# Sheet5.net
KiCad netlist of a schematic drawn in Altium Designer
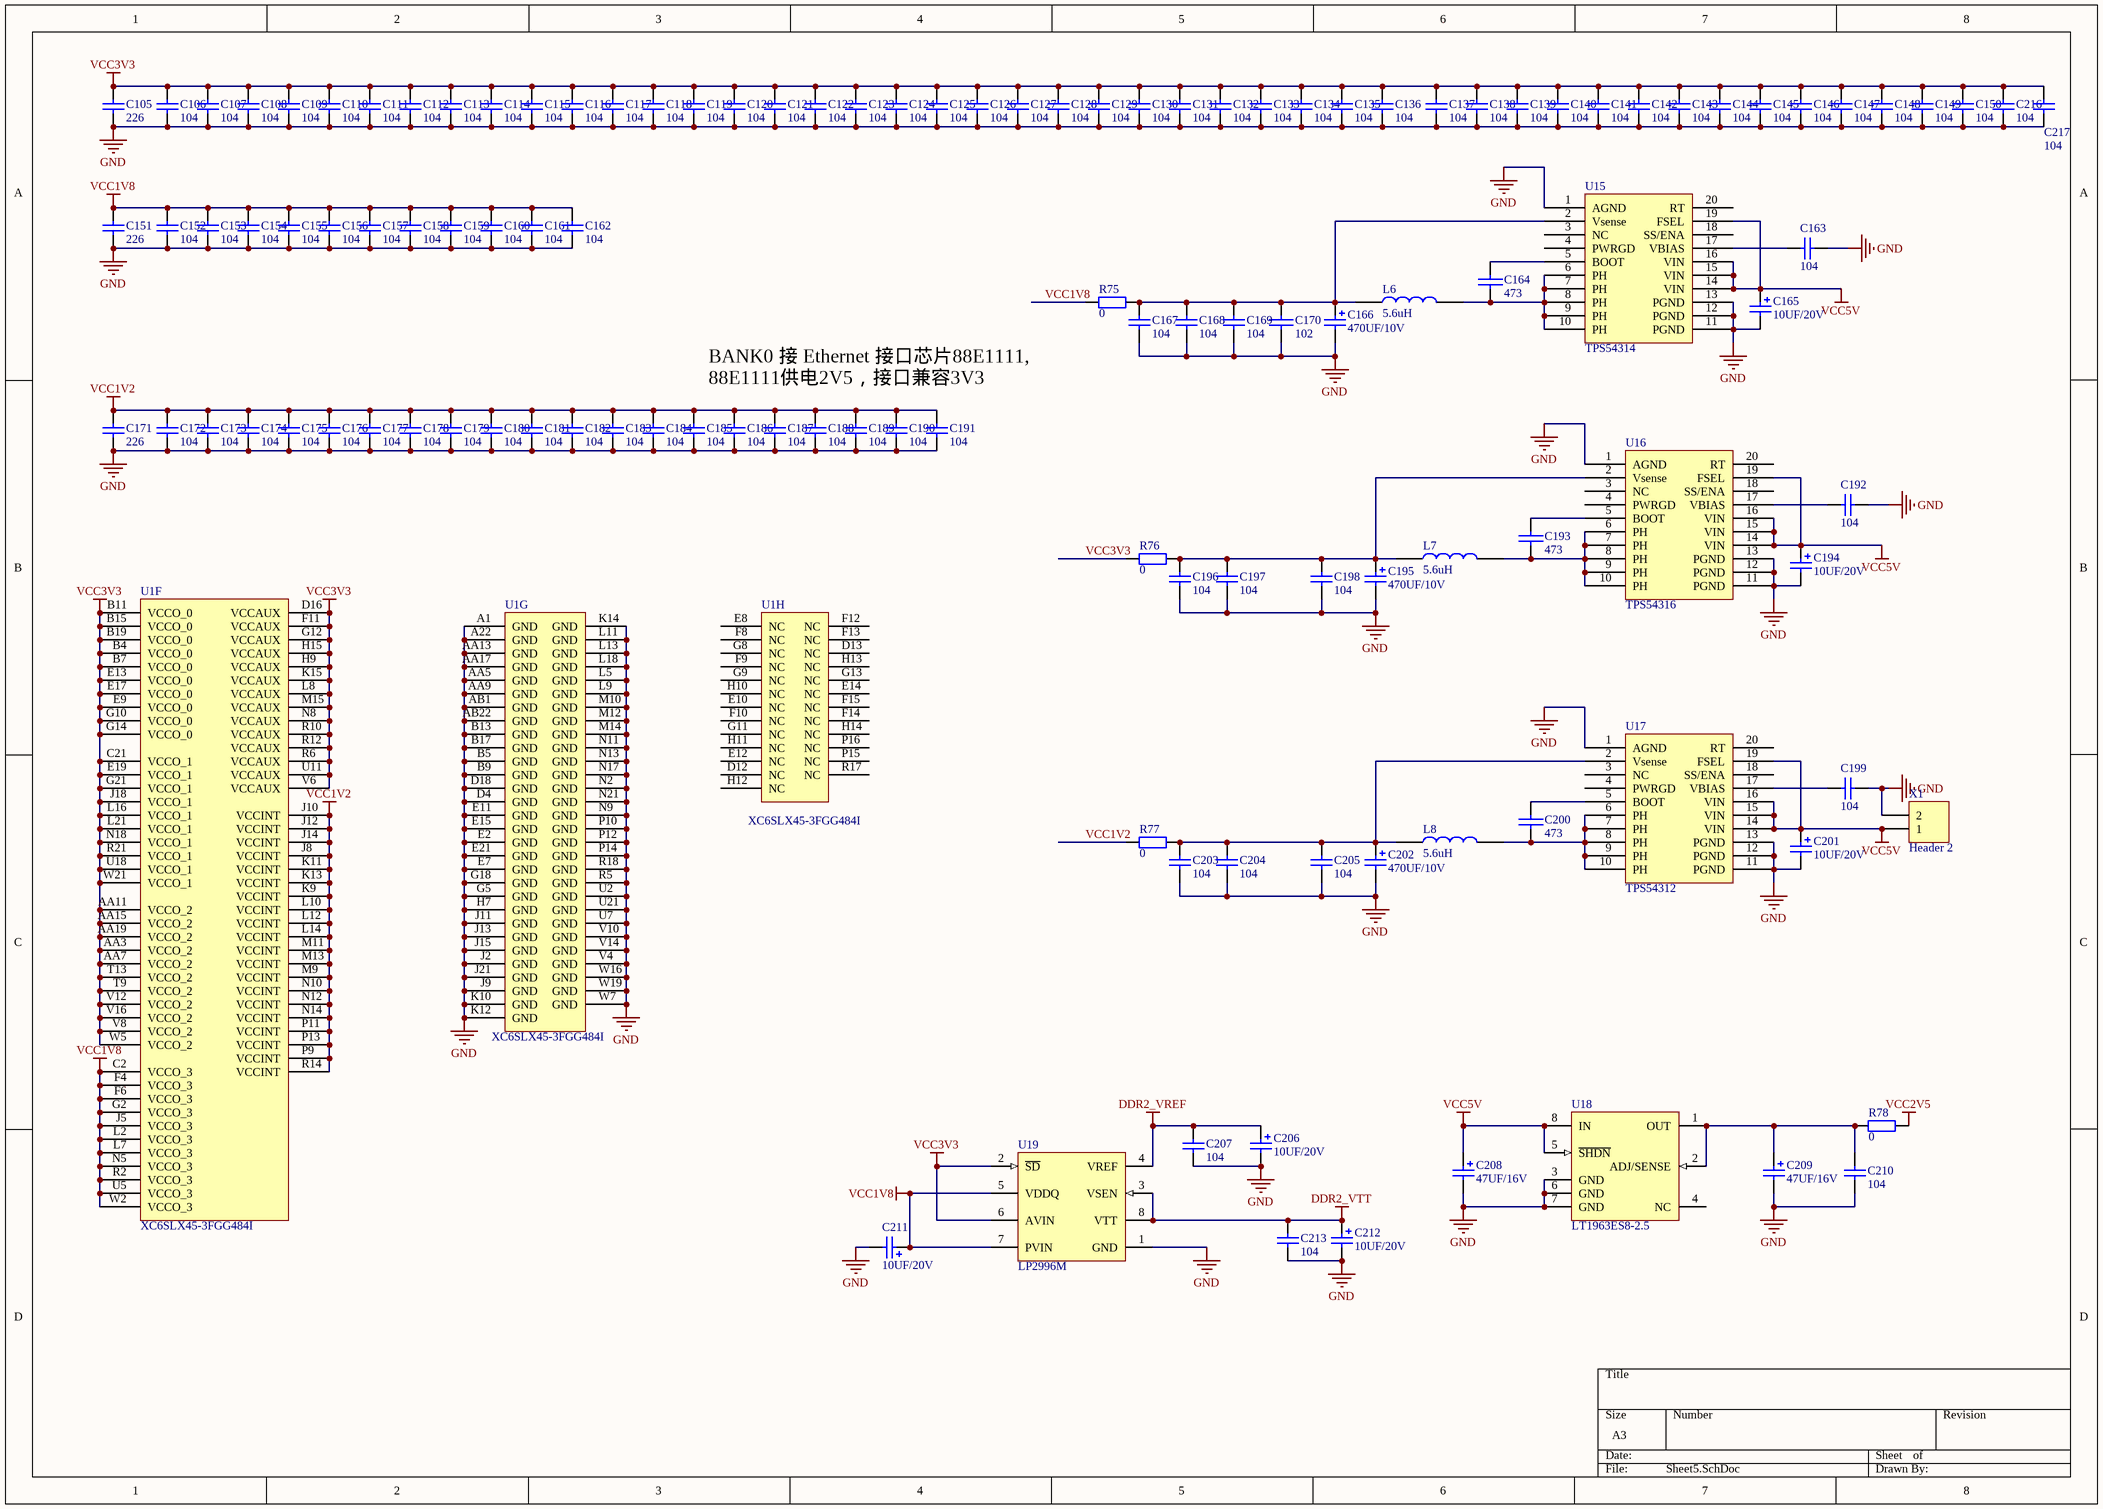
[diagram p0: Sheet5.SchDoc]

(export (version "E")
  (design (tool "Eeschema 10.0.6"))
  (components
    (comp (ref "C105")
      (value "226")
      (footprint "0603")
      (description "Capacitor")
      (fields (field (name "PUBLISHER") "Altium Limited"))
      (libsource (lib "Miscellaneous Devices") (part "Cap"))
    )
    (comp (ref "C106")
      (value "104")
      (footprint "0402")
      (description "Capacitor")
      (fields (field (name "PUBLISHER") "Altium Limited"))
      (libsource (lib "Miscellaneous Devices") (part "Cap"))
    )
    (comp (ref "C107")
      (value "104")
      (footprint "0402")
      (description "Capacitor")
      (fields (field (name "PUBLISHER") "Altium Limited"))
      (libsource (lib "Miscellaneous Devices") (part "Cap"))
    )
    (comp (ref "C108")
      (value "104")
      (footprint "0402")
      (description "Capacitor")
      (fields (field (name "PUBLISHER") "Altium Limited"))
      (libsource (lib "Miscellaneous Devices") (part "Cap"))
    )
    (comp (ref "C109")
      (value "104")
      (footprint "0402")
      (description "Capacitor")
      (fields (field (name "PUBLISHER") "Altium Limited"))
      (libsource (lib "Miscellaneous Devices") (part "Cap"))
    )
    (comp (ref "C110")
      (value "104")
      (footprint "0402")
      (description "Capacitor")
      (fields (field (name "PUBLISHER") "Altium Limited"))
      (libsource (lib "Miscellaneous Devices") (part "Cap"))
    )
    (comp (ref "C111")
      (value "104")
      (footprint "0402")
      (description "Capacitor")
      (fields (field (name "PUBLISHER") "Altium Limited"))
      (libsource (lib "Miscellaneous Devices") (part "Cap"))
    )
    (comp (ref "C112")
      (value "104")
      (footprint "0402")
      (description "Capacitor")
      (fields (field (name "PUBLISHER") "Altium Limited"))
      (libsource (lib "Miscellaneous Devices") (part "Cap"))
    )
    (comp (ref "C113")
      (value "104")
      (footprint "0402")
      (description "Capacitor")
      (fields (field (name "PUBLISHER") "Altium Limited"))
      (libsource (lib "Miscellaneous Devices") (part "Cap"))
    )
    (comp (ref "C114")
      (value "104")
      (footprint "0402")
      (description "Capacitor")
      (fields (field (name "PUBLISHER") "Altium Limited"))
      (libsource (lib "Miscellaneous Devices") (part "Cap"))
    )
    (comp (ref "C115")
      (value "104")
      (footprint "0402")
      (description "Capacitor")
      (fields (field (name "PUBLISHER") "Altium Limited"))
      (libsource (lib "Miscellaneous Devices") (part "Cap"))
    )
    (comp (ref "C116")
      (value "104")
      (footprint "0402")
      (description "Capacitor")
      (fields (field (name "PUBLISHER") "Altium Limited"))
      (libsource (lib "Miscellaneous Devices") (part "Cap"))
    )
    (comp (ref "C117")
      (value "104")
      (footprint "0402")
      (description "Capacitor")
      (fields (field (name "PUBLISHER") "Altium Limited"))
      (libsource (lib "Miscellaneous Devices") (part "Cap"))
    )
    (comp (ref "C118")
      (value "104")
      (footprint "0402")
      (description "Capacitor")
      (fields (field (name "PUBLISHER") "Altium Limited"))
      (libsource (lib "Miscellaneous Devices") (part "Cap"))
    )
    (comp (ref "C119")
      (value "104")
      (footprint "0402")
      (description "Capacitor")
      (fields (field (name "PUBLISHER") "Altium Limited"))
      (libsource (lib "Miscellaneous Devices") (part "Cap"))
    )
    (comp (ref "C120")
      (value "104")
      (footprint "0402")
      (description "Capacitor")
      (fields (field (name "PUBLISHER") "Altium Limited"))
      (libsource (lib "Miscellaneous Devices") (part "Cap"))
    )
    (comp (ref "C121")
      (value "104")
      (footprint "0402")
      (description "Capacitor")
      (fields (field (name "PUBLISHER") "Altium Limited"))
      (libsource (lib "Miscellaneous Devices") (part "Cap"))
    )
    (comp (ref "C122")
      (value "104")
      (footprint "0402")
      (description "Capacitor")
      (fields (field (name "PUBLISHER") "Altium Limited"))
      (libsource (lib "Miscellaneous Devices") (part "Cap"))
    )
    (comp (ref "C123")
      (value "104")
      (footprint "0402")
      (description "Capacitor")
      (fields (field (name "PUBLISHER") "Altium Limited"))
      (libsource (lib "Miscellaneous Devices") (part "Cap"))
    )
    (comp (ref "C124")
      (value "104")
      (footprint "0402")
      (description "Capacitor")
      (fields (field (name "PUBLISHER") "Altium Limited"))
      (libsource (lib "Miscellaneous Devices") (part "Cap"))
    )
    (comp (ref "C125")
      (value "104")
      (footprint "0402")
      (description "Capacitor")
      (fields (field (name "PUBLISHER") "Altium Limited"))
      (libsource (lib "Miscellaneous Devices") (part "Cap"))
    )
    (comp (ref "C126")
      (value "104")
      (footprint "0402")
      (description "Capacitor")
      (fields (field (name "PUBLISHER") "Altium Limited"))
      (libsource (lib "Miscellaneous Devices") (part "Cap"))
    )
    (comp (ref "C127")
      (value "104")
      (footprint "0402")
      (description "Capacitor")
      (fields (field (name "PUBLISHER") "Altium Limited"))
      (libsource (lib "Miscellaneous Devices") (part "Cap"))
    )
    (comp (ref "C128")
      (value "104")
      (footprint "0402")
      (description "Capacitor")
      (fields (field (name "PUBLISHER") "Altium Limited"))
      (libsource (lib "Miscellaneous Devices") (part "Cap"))
    )
    (comp (ref "C129")
      (value "104")
      (footprint "0402")
      (description "Capacitor")
      (fields (field (name "PUBLISHER") "Altium Limited"))
      (libsource (lib "Miscellaneous Devices") (part "Cap"))
    )
    (comp (ref "C130")
      (value "104")
      (footprint "0402")
      (description "Capacitor")
      (fields (field (name "PUBLISHER") "Altium Limited"))
      (libsource (lib "Miscellaneous Devices") (part "Cap"))
    )
    (comp (ref "C131")
      (value "104")
      (footprint "0402")
      (description "Capacitor")
      (fields (field (name "PUBLISHER") "Altium Limited"))
      (libsource (lib "Miscellaneous Devices") (part "Cap"))
    )
    (comp (ref "C132")
      (value "104")
      (footprint "0402")
      (description "Capacitor")
      (fields (field (name "PUBLISHER") "Altium Limited"))
      (libsource (lib "Miscellaneous Devices") (part "Cap"))
    )
    (comp (ref "C133")
      (value "104")
      (footprint "0402")
      (description "Capacitor")
      (fields (field (name "PUBLISHER") "Altium Limited"))
      (libsource (lib "Miscellaneous Devices") (part "Cap"))
    )
    (comp (ref "C134")
      (value "104")
      (footprint "0402")
      (description "Capacitor")
      (fields (field (name "PUBLISHER") "Altium Limited"))
      (libsource (lib "Miscellaneous Devices") (part "Cap"))
    )
    (comp (ref "C135")
      (value "104")
      (footprint "0402")
      (description "Capacitor")
      (fields (field (name "PUBLISHER") "Altium Limited"))
      (libsource (lib "Miscellaneous Devices") (part "Cap"))
    )
    (comp (ref "C136")
      (value "104")
      (footprint "0402")
      (description "Capacitor")
      (fields (field (name "PUBLISHER") "Altium Limited"))
      (libsource (lib "Miscellaneous Devices") (part "Cap"))
    )
    (comp (ref "C137")
      (value "104")
      (footprint "0402")
      (description "Capacitor")
      (fields (field (name "PUBLISHER") "Altium Limited"))
      (libsource (lib "Miscellaneous Devices") (part "Cap"))
    )
    (comp (ref "C138")
      (value "104")
      (footprint "0402")
      (description "Capacitor")
      (fields (field (name "PUBLISHER") "Altium Limited"))
      (libsource (lib "Miscellaneous Devices") (part "Cap"))
    )
    (comp (ref "C139")
      (value "104")
      (footprint "0402")
      (description "Capacitor")
      (fields (field (name "PUBLISHER") "Altium Limited"))
      (libsource (lib "Miscellaneous Devices") (part "Cap"))
    )
    (comp (ref "C140")
      (value "104")
      (footprint "0402")
      (description "Capacitor")
      (fields (field (name "PUBLISHER") "Altium Limited"))
      (libsource (lib "Miscellaneous Devices") (part "Cap"))
    )
    (comp (ref "C141")
      (value "104")
      (footprint "0402")
      (description "Capacitor")
      (fields (field (name "PUBLISHER") "Altium Limited"))
      (libsource (lib "Miscellaneous Devices") (part "Cap"))
    )
    (comp (ref "C142")
      (value "104")
      (footprint "0402")
      (description "Capacitor")
      (fields (field (name "PUBLISHER") "Altium Limited"))
      (libsource (lib "Miscellaneous Devices") (part "Cap"))
    )
    (comp (ref "C143")
      (value "104")
      (footprint "0402")
      (description "Capacitor")
      (fields (field (name "PUBLISHER") "Altium Limited"))
      (libsource (lib "Miscellaneous Devices") (part "Cap"))
    )
    (comp (ref "C144")
      (value "104")
      (footprint "0402")
      (description "Capacitor")
      (fields (field (name "PUBLISHER") "Altium Limited"))
      (libsource (lib "Miscellaneous Devices") (part "Cap"))
    )
    (comp (ref "C145")
      (value "104")
      (footprint "0402")
      (description "Capacitor")
      (fields (field (name "PUBLISHER") "Altium Limited"))
      (libsource (lib "Miscellaneous Devices") (part "Cap"))
    )
    (comp (ref "C146")
      (value "104")
      (footprint "0402")
      (description "Capacitor")
      (fields (field (name "PUBLISHER") "Altium Limited"))
      (libsource (lib "Miscellaneous Devices") (part "Cap"))
    )
    (comp (ref "C147")
      (value "104")
      (footprint "0402")
      (description "Capacitor")
      (fields (field (name "PUBLISHER") "Altium Limited"))
      (libsource (lib "Miscellaneous Devices") (part "Cap"))
    )
    (comp (ref "C148")
      (value "104")
      (footprint "0402")
      (description "Capacitor")
      (fields (field (name "PUBLISHER") "Altium Limited"))
      (libsource (lib "Miscellaneous Devices") (part "Cap"))
    )
    (comp (ref "C149")
      (value "104")
      (footprint "0402")
      (description "Capacitor")
      (fields (field (name "PUBLISHER") "Altium Limited"))
      (libsource (lib "Miscellaneous Devices") (part "Cap"))
    )
    (comp (ref "C150")
      (value "104")
      (footprint "0402")
      (description "Capacitor")
      (fields (field (name "PUBLISHER") "Altium Limited"))
      (libsource (lib "Miscellaneous Devices") (part "Cap"))
    )
    (comp (ref "C151")
      (value "226")
      (footprint "0603")
      (description "Capacitor")
      (fields (field (name "PUBLISHER") "Altium Limited"))
      (libsource (lib "Miscellaneous Devices") (part "Cap"))
    )
    (comp (ref "C152")
      (value "104")
      (footprint "0402")
      (description "Capacitor")
      (fields (field (name "PUBLISHER") "Altium Limited"))
      (libsource (lib "Miscellaneous Devices") (part "Cap"))
    )
    (comp (ref "C153")
      (value "104")
      (footprint "0402")
      (description "Capacitor")
      (fields (field (name "PUBLISHER") "Altium Limited"))
      (libsource (lib "Miscellaneous Devices") (part "Cap"))
    )
    (comp (ref "C154")
      (value "104")
      (footprint "0402")
      (description "Capacitor")
      (fields (field (name "PUBLISHER") "Altium Limited"))
      (libsource (lib "Miscellaneous Devices") (part "Cap"))
    )
    (comp (ref "C155")
      (value "104")
      (footprint "0402")
      (description "Capacitor")
      (fields (field (name "PUBLISHER") "Altium Limited"))
      (libsource (lib "Miscellaneous Devices") (part "Cap"))
    )
    (comp (ref "C156")
      (value "104")
      (footprint "0402")
      (description "Capacitor")
      (fields (field (name "PUBLISHER") "Altium Limited"))
      (libsource (lib "Miscellaneous Devices") (part "Cap"))
    )
    (comp (ref "C157")
      (value "104")
      (footprint "0402")
      (description "Capacitor")
      (fields (field (name "PUBLISHER") "Altium Limited"))
      (libsource (lib "Miscellaneous Devices") (part "Cap"))
    )
    (comp (ref "C158")
      (value "104")
      (footprint "0402")
      (description "Capacitor")
      (fields (field (name "PUBLISHER") "Altium Limited"))
      (libsource (lib "Miscellaneous Devices") (part "Cap"))
    )
    (comp (ref "C159")
      (value "104")
      (footprint "0402")
      (description "Capacitor")
      (fields (field (name "PUBLISHER") "Altium Limited"))
      (libsource (lib "Miscellaneous Devices") (part "Cap"))
    )
    (comp (ref "C160")
      (value "104")
      (footprint "0402")
      (description "Capacitor")
      (fields (field (name "PUBLISHER") "Altium Limited"))
      (libsource (lib "Miscellaneous Devices") (part "Cap"))
    )
    (comp (ref "C161")
      (value "104")
      (footprint "0402")
      (description "Capacitor")
      (fields (field (name "PUBLISHER") "Altium Limited"))
      (libsource (lib "Miscellaneous Devices") (part "Cap"))
    )
    (comp (ref "C162")
      (value "104")
      (footprint "0402")
      (description "Capacitor")
      (fields (field (name "PUBLISHER") "Altium Limited"))
      (libsource (lib "Miscellaneous Devices") (part "Cap"))
    )
    (comp (ref "C163")
      (value "104")
      (footprint "0402")
      (description "Capacitor")
      (fields (field (name "PUBLISHER") "Altium Limited"))
      (libsource (lib "Miscellaneous Devices") (part "Cap"))
    )
    (comp (ref "C164")
      (value "473")
      (footprint "0402")
      (description "Capacitor")
      (libsource (lib "*") (part "CAP"))
    )
    (comp (ref "C165")
      (value "10UF/20V")
      (footprint "CAP-B")
      (description "Polarized Capacitor (Axial)")
      (fields (field (name "PUBLISHER") "Altium Limited"))
      (libsource (lib "Miscellaneous Devices") (part "Cap Pol2"))
    )
    (comp (ref "C166")
      (value "470UF/10V")
      (footprint "CAP-D")
      (description "Polarized Capacitor (Axial)")
      (fields (field (name "PUBLISHER") "Altium Limited"))
      (libsource (lib "Miscellaneous Devices") (part "Cap Pol2"))
    )
    (comp (ref "C167")
      (value "104")
      (footprint "0402")
      (description "Capacitor")
      (fields (field (name "PUBLISHER") "Altium Limited"))
      (libsource (lib "Miscellaneous Devices") (part "Cap"))
    )
    (comp (ref "C168")
      (value "104")
      (footprint "0402")
      (description "Capacitor")
      (fields (field (name "PUBLISHER") "Altium Limited"))
      (libsource (lib "Miscellaneous Devices") (part "Cap"))
    )
    (comp (ref "C169")
      (value "104")
      (footprint "0402")
      (description "Capacitor")
      (fields (field (name "PUBLISHER") "Altium Limited"))
      (libsource (lib "Miscellaneous Devices") (part "Cap"))
    )
    (comp (ref "C170")
      (value "102")
      (footprint "0402")
      (description "Capacitor")
      (libsource (lib "*") (part "CAP"))
    )
    (comp (ref "C171")
      (value "226")
      (footprint "0603")
      (description "Capacitor")
      (fields (field (name "PUBLISHER") "Altium Limited"))
      (libsource (lib "Miscellaneous Devices") (part "Cap"))
    )
    (comp (ref "C172")
      (value "104")
      (footprint "0402")
      (description "Capacitor")
      (fields (field (name "PUBLISHER") "Altium Limited"))
      (libsource (lib "Miscellaneous Devices") (part "Cap"))
    )
    (comp (ref "C173")
      (value "104")
      (footprint "0402")
      (description "Capacitor")
      (fields (field (name "PUBLISHER") "Altium Limited"))
      (libsource (lib "Miscellaneous Devices") (part "Cap"))
    )
    (comp (ref "C174")
      (value "104")
      (footprint "0402")
      (description "Capacitor")
      (fields (field (name "PUBLISHER") "Altium Limited"))
      (libsource (lib "Miscellaneous Devices") (part "Cap"))
    )
    (comp (ref "C175")
      (value "104")
      (footprint "0402")
      (description "Capacitor")
      (fields (field (name "PUBLISHER") "Altium Limited"))
      (libsource (lib "Miscellaneous Devices") (part "Cap"))
    )
    (comp (ref "C176")
      (value "104")
      (footprint "0402")
      (description "Capacitor")
      (fields (field (name "PUBLISHER") "Altium Limited"))
      (libsource (lib "Miscellaneous Devices") (part "Cap"))
    )
    (comp (ref "C177")
      (value "104")
      (footprint "0402")
      (description "Capacitor")
      (fields (field (name "PUBLISHER") "Altium Limited"))
      (libsource (lib "Miscellaneous Devices") (part "Cap"))
    )
    (comp (ref "C178")
      (value "104")
      (footprint "0402")
      (description "Capacitor")
      (fields (field (name "PUBLISHER") "Altium Limited"))
      (libsource (lib "Miscellaneous Devices") (part "Cap"))
    )
    (comp (ref "C179")
      (value "104")
      (footprint "0402")
      (description "Capacitor")
      (fields (field (name "PUBLISHER") "Altium Limited"))
      (libsource (lib "Miscellaneous Devices") (part "Cap"))
    )
    (comp (ref "C180")
      (value "104")
      (footprint "0402")
      (description "Capacitor")
      (fields (field (name "PUBLISHER") "Altium Limited"))
      (libsource (lib "Miscellaneous Devices") (part "Cap"))
    )
    (comp (ref "C181")
      (value "104")
      (footprint "0402")
      (description "Capacitor")
      (fields (field (name "PUBLISHER") "Altium Limited"))
      (libsource (lib "Miscellaneous Devices") (part "Cap"))
    )
    (comp (ref "C182")
      (value "104")
      (footprint "0402")
      (description "Capacitor")
      (fields (field (name "PUBLISHER") "Altium Limited"))
      (libsource (lib "Miscellaneous Devices") (part "Cap"))
    )
    (comp (ref "C183")
      (value "104")
      (footprint "0402")
      (description "Capacitor")
      (fields (field (name "PUBLISHER") "Altium Limited"))
      (libsource (lib "Miscellaneous Devices") (part "Cap"))
    )
    (comp (ref "C184")
      (value "104")
      (footprint "0402")
      (description "Capacitor")
      (fields (field (name "PUBLISHER") "Altium Limited"))
      (libsource (lib "Miscellaneous Devices") (part "Cap"))
    )
    (comp (ref "C185")
      (value "104")
      (footprint "0402")
      (description "Capacitor")
      (fields (field (name "PUBLISHER") "Altium Limited"))
      (libsource (lib "Miscellaneous Devices") (part "Cap"))
    )
    (comp (ref "C186")
      (value "104")
      (footprint "0402")
      (description "Capacitor")
      (fields (field (name "PUBLISHER") "Altium Limited"))
      (libsource (lib "Miscellaneous Devices") (part "Cap"))
    )
    (comp (ref "C187")
      (value "104")
      (footprint "0402")
      (description "Capacitor")
      (fields (field (name "PUBLISHER") "Altium Limited"))
      (libsource (lib "Miscellaneous Devices") (part "Cap"))
    )
    (comp (ref "C188")
      (value "104")
      (footprint "0402")
      (description "Capacitor")
      (fields (field (name "PUBLISHER") "Altium Limited"))
      (libsource (lib "Miscellaneous Devices") (part "Cap"))
    )
    (comp (ref "C189")
      (value "104")
      (footprint "0402")
      (description "Capacitor")
      (fields (field (name "PUBLISHER") "Altium Limited"))
      (libsource (lib "Miscellaneous Devices") (part "Cap"))
    )
    (comp (ref "C190")
      (value "104")
      (footprint "0402")
      (description "Capacitor")
      (fields (field (name "PUBLISHER") "Altium Limited"))
      (libsource (lib "Miscellaneous Devices") (part "Cap"))
    )
    (comp (ref "C191")
      (value "104")
      (footprint "0402")
      (description "Capacitor")
      (fields (field (name "PUBLISHER") "Altium Limited"))
      (libsource (lib "Miscellaneous Devices") (part "Cap"))
    )
    (comp (ref "C192")
      (value "104")
      (footprint "0402")
      (description "Capacitor")
      (fields (field (name "PUBLISHER") "Altium Limited"))
      (libsource (lib "Miscellaneous Devices") (part "Cap"))
    )
    (comp (ref "C193")
      (value "473")
      (footprint "0402")
      (description "Capacitor")
      (libsource (lib "*") (part "CAP"))
    )
    (comp (ref "C194")
      (value "10UF/20V")
      (footprint "CAP-B")
      (description "Polarized Capacitor (Axial)")
      (fields (field (name "PUBLISHER") "Altium Limited"))
      (libsource (lib "Miscellaneous Devices") (part "Cap Pol2"))
    )
    (comp (ref "C195")
      (value "470UF/10V")
      (footprint "CAP-D")
      (description "Polarized Capacitor (Axial)")
      (fields (field (name "PUBLISHER") "Altium Limited"))
      (libsource (lib "Miscellaneous Devices") (part "Cap Pol2"))
    )
    (comp (ref "C196")
      (value "104")
      (footprint "0402")
      (description "Capacitor")
      (fields (field (name "PUBLISHER") "Altium Limited"))
      (libsource (lib "Miscellaneous Devices") (part "Cap"))
    )
    (comp (ref "C197")
      (value "104")
      (footprint "0402")
      (description "Capacitor")
      (fields (field (name "PUBLISHER") "Altium Limited"))
      (libsource (lib "Miscellaneous Devices") (part "Cap"))
    )
    (comp (ref "C198")
      (value "104")
      (footprint "0402")
      (description "Capacitor")
      (fields (field (name "PUBLISHER") "Altium Limited"))
      (libsource (lib "Miscellaneous Devices") (part "Cap"))
    )
    (comp (ref "C199")
      (value "104")
      (footprint "0402")
      (description "Capacitor")
      (fields (field (name "PUBLISHER") "Altium Limited"))
      (libsource (lib "Miscellaneous Devices") (part "Cap"))
    )
    (comp (ref "C200")
      (value "473")
      (footprint "0402")
      (description "Capacitor")
      (libsource (lib "*") (part "CAP"))
    )
    (comp (ref "C201")
      (value "10UF/20V")
      (footprint "CAP-B")
      (description "Polarized Capacitor (Axial)")
      (fields (field (name "PUBLISHER") "Altium Limited"))
      (libsource (lib "Miscellaneous Devices") (part "Cap Pol2"))
    )
    (comp (ref "C202")
      (value "470UF/10V")
      (footprint "CAP-D")
      (description "Polarized Capacitor (Axial)")
      (fields (field (name "PUBLISHER") "Altium Limited"))
      (libsource (lib "Miscellaneous Devices") (part "Cap Pol2"))
    )
    (comp (ref "C203")
      (value "104")
      (footprint "0402")
      (description "Capacitor")
      (fields (field (name "PUBLISHER") "Altium Limited"))
      (libsource (lib "Miscellaneous Devices") (part "Cap"))
    )
    (comp (ref "C204")
      (value "104")
      (footprint "0402")
      (description "Capacitor")
      (fields (field (name "PUBLISHER") "Altium Limited"))
      (libsource (lib "Miscellaneous Devices") (part "Cap"))
    )
    (comp (ref "C205")
      (value "104")
      (footprint "0402")
      (description "Capacitor")
      (fields (field (name "PUBLISHER") "Altium Limited"))
      (libsource (lib "Miscellaneous Devices") (part "Cap"))
    )
    (comp (ref "C206")
      (value "10UF/20V")
      (footprint "CAP-B")
      (description "Polarized Capacitor (Axial)")
      (fields (field (name "PUBLISHER") "Altium Limited"))
      (libsource (lib "Miscellaneous Devices") (part "Cap Pol2"))
    )
    (comp (ref "C207")
      (value "104")
      (footprint "0402")
      (description "Capacitor")
      (fields (field (name "PUBLISHER") "Altium Limited"))
      (libsource (lib "Miscellaneous Devices") (part "Cap"))
    )
    (comp (ref "C208")
      (value "47UF/16V")
      (footprint "CAP-C")
      (description "Polarized Capacitor (Axial)")
      (fields (field (name "PUBLISHER") "Altium Limited"))
      (libsource (lib "Miscellaneous Devices") (part "Cap Pol2"))
    )
    (comp (ref "C209")
      (value "47UF/16V")
      (footprint "CAP-C")
      (description "Polarized Capacitor (Axial)")
      (fields (field (name "PUBLISHER") "Altium Limited"))
      (libsource (lib "Miscellaneous Devices") (part "Cap Pol2"))
    )
    (comp (ref "C210")
      (value "104")
      (footprint "0402")
      (description "Capacitor")
      (fields (field (name "PUBLISHER") "Altium Limited"))
      (libsource (lib "Miscellaneous Devices") (part "Cap"))
    )
    (comp (ref "C211")
      (value "10UF/20V")
      (footprint "CAP-B")
      (description "Polarized Capacitor (Axial)")
      (fields (field (name "PUBLISHER") "Altium Limited"))
      (libsource (lib "Miscellaneous Devices") (part "Cap Pol2"))
    )
    (comp (ref "C212")
      (value "10UF/20V")
      (footprint "CAP-B")
      (description "Polarized Capacitor (Axial)")
      (fields (field (name "PUBLISHER") "Altium Limited"))
      (libsource (lib "Miscellaneous Devices") (part "Cap Pol2"))
    )
    (comp (ref "C213")
      (value "104")
      (footprint "0402")
      (description "Capacitor")
      (fields (field (name "PUBLISHER") "Altium Limited"))
      (libsource (lib "Miscellaneous Devices") (part "Cap"))
    )
    (comp (ref "C216")
      (value "104")
      (footprint "0402")
      (description "Capacitor")
      (fields (field (name "PUBLISHER") "Altium Limited"))
      (libsource (lib "Miscellaneous Devices") (part "Cap"))
    )
    (comp (ref "C217")
      (value "104")
      (footprint "0402")
      (description "Capacitor")
      (fields (field (name "PUBLISHER") "Altium Limited"))
      (libsource (lib "Miscellaneous Devices") (part "Cap"))
    )
    (comp (ref "L6") (value "5.6uH") (footprint "L5R2") (libsource (lib "*") (part "INDUCTOR1")))
    (comp (ref "L7") (value "5.6uH") (footprint "L5R2") (libsource (lib "*") (part "INDUCTOR1")))
    (comp (ref "L8") (value "5.6uH") (footprint "L5R2") (libsource (lib "*") (part "INDUCTOR1")))
    (comp (ref "R75")
      (value "0")
      (footprint "0603")
      (description "Resistor")
      (fields (field (name "PUBLISHER") "Altium Limited"))
      (libsource (lib "Miscellaneous Devices") (part "Res2"))
    )
    (comp (ref "R76")
      (value "0")
      (footprint "0603")
      (description "Resistor")
      (fields (field (name "PUBLISHER") "Altium Limited"))
      (libsource (lib "Miscellaneous Devices") (part "Res2"))
    )
    (comp (ref "R77")
      (value "0")
      (footprint "0603")
      (description "Resistor")
      (fields (field (name "PUBLISHER") "Altium Limited"))
      (libsource (lib "Miscellaneous Devices") (part "Res2"))
    )
    (comp (ref "R78")
      (value "0")
      (footprint "0603")
      (description "Resistor")
      (fields (field (name "PUBLISHER") "Altium Limited"))
      (libsource (lib "Miscellaneous Devices") (part "Res2"))
    )
    (comp (ref "U1")
      (value "XC6SLX45-3FGG484I")
      (footprint "FGG484")
      (fields (field (name "PUBLISHER") "Altium Limited"))
      (libsource (lib "Xilinx Spartan-6") (part "XC6SLX45-3FGG484I"))
    )
    (comp (ref "U15")
      (value "TPS54314")
      (footprint "SOP20")
      (description "TPS54312")
      (libsource (lib "*") (part "TPS54312"))
    )
    (comp (ref "U16")
      (value "TPS54316")
      (footprint "SOP20")
      (description "TPS54312")
      (libsource (lib "*") (part "TPS54312"))
    )
    (comp (ref "U17") (value "TPS54312") (footprint "SOP20") (libsource (lib "*") (part "TPS54312")))
    (comp (ref "U18")
      (value "LT1963ES8-2.5")
      (footprint "so_8")
      (description "300mA, Low Noise, Micropower Low Dropout Regulator")
      (fields (field (name "PUBLISHER") "Altium Limited"))
      (libsource (lib "Mpd_Fpga_2") (part "LT1962EMS8"))
    )
    (comp (ref "U19")
      (value "LP2996M")
      (footprint "so_8")
      (description "DDR Termination Regulator")
      (fields
        (field (name "MANUFACTURER") "National Semiconductor")
        (field (name "DIGIKEYPARTNUMBER") "LP2996M-ND")
        (field (name "PUBLISHER") "Altium Limited")
      )
      (libsource (lib "NSC MiscPower") (part "LP2996M"))
    )
    (comp (ref "X1")
      (value "Header 2")
      (footprint "HDR1X2")
      (description "Header, 2-Pin")
      (fields (field (name "PUBLISHER") "Altium Limited"))
      (libsource (lib "Miscellaneous Connectors") (part "Header 2"))
    )
  )
  (nets
    (net (code "1") (name "DDR2_VREF") (class "Default")
      (node (ref "C206") (pin "1") (pinfunction "1_1") (pintype "passive"))
      (node (ref "C207") (pin "2") (pinfunction "2_2") (pintype "passive"))
      (node (ref "U19") (pin "4") (pinfunction "VREF_4") (pintype "passive"))
    )
    (net (code "2") (name "DDR2_VTT") (class "Default")
      (node (ref "C212") (pin "1") (pinfunction "1_1") (pintype "passive"))
      (node (ref "C213") (pin "2") (pinfunction "2_2") (pintype "passive"))
      (node (ref "U19") (pin "3") (pinfunction "VSEN_3") (pintype "input"))
      (node (ref "U19") (pin "8") (pinfunction "VTT_8") (pintype "power_in"))
    )
    (net (code "3") (name "GND") (class "Default")
      (node (ref "C105") (pin "1") (pinfunction "1_1") (pintype "passive"))
      (node (ref "C106") (pin "1") (pinfunction "1_1") (pintype "passive"))
      (node (ref "C107") (pin "1") (pinfunction "1_1") (pintype "passive"))
      (node (ref "C108") (pin "1") (pinfunction "1_1") (pintype "passive"))
      (node (ref "C109") (pin "1") (pinfunction "1_1") (pintype "passive"))
      (node (ref "C110") (pin "1") (pinfunction "1_1") (pintype "passive"))
      (node (ref "C111") (pin "1") (pinfunction "1_1") (pintype "passive"))
      (node (ref "C112") (pin "1") (pinfunction "1_1") (pintype "passive"))
      (node (ref "C113") (pin "1") (pinfunction "1_1") (pintype "passive"))
      (node (ref "C114") (pin "1") (pinfunction "1_1") (pintype "passive"))
      (node (ref "C115") (pin "1") (pinfunction "1_1") (pintype "passive"))
      (node (ref "C116") (pin "1") (pinfunction "1_1") (pintype "passive"))
      (node (ref "C117") (pin "1") (pinfunction "1_1") (pintype "passive"))
      (node (ref "C118") (pin "1") (pinfunction "1_1") (pintype "passive"))
      (node (ref "C119") (pin "1") (pinfunction "1_1") (pintype "passive"))
      (node (ref "C120") (pin "1") (pinfunction "1_1") (pintype "passive"))
      (node (ref "C121") (pin "1") (pinfunction "1_1") (pintype "passive"))
      (node (ref "C122") (pin "1") (pinfunction "1_1") (pintype "passive"))
      (node (ref "C123") (pin "1") (pinfunction "1_1") (pintype "passive"))
      (node (ref "C124") (pin "1") (pinfunction "1_1") (pintype "passive"))
      (node (ref "C125") (pin "1") (pinfunction "1_1") (pintype "passive"))
      (node (ref "C126") (pin "1") (pinfunction "1_1") (pintype "passive"))
      (node (ref "C127") (pin "1") (pinfunction "1_1") (pintype "passive"))
      (node (ref "C128") (pin "1") (pinfunction "1_1") (pintype "passive"))
      (node (ref "C129") (pin "1") (pinfunction "1_1") (pintype "passive"))
      (node (ref "C130") (pin "1") (pinfunction "1_1") (pintype "passive"))
      (node (ref "C131") (pin "1") (pinfunction "1_1") (pintype "passive"))
      (node (ref "C132") (pin "1") (pinfunction "1_1") (pintype "passive"))
      (node (ref "C133") (pin "1") (pinfunction "1_1") (pintype "passive"))
      (node (ref "C134") (pin "1") (pinfunction "1_1") (pintype "passive"))
      (node (ref "C135") (pin "1") (pinfunction "1_1") (pintype "passive"))
      (node (ref "C136") (pin "1") (pinfunction "1_1") (pintype "passive"))
      (node (ref "C137") (pin "1") (pinfunction "1_1") (pintype "passive"))
      (node (ref "C138") (pin "1") (pinfunction "1_1") (pintype "passive"))
      (node (ref "C139") (pin "1") (pinfunction "1_1") (pintype "passive"))
      (node (ref "C140") (pin "1") (pinfunction "1_1") (pintype "passive"))
      (node (ref "C141") (pin "1") (pinfunction "1_1") (pintype "passive"))
      (node (ref "C142") (pin "1") (pinfunction "1_1") (pintype "passive"))
      (node (ref "C143") (pin "1") (pinfunction "1_1") (pintype "passive"))
      (node (ref "C144") (pin "1") (pinfunction "1_1") (pintype "passive"))
      (node (ref "C145") (pin "1") (pinfunction "1_1") (pintype "passive"))
      (node (ref "C146") (pin "1") (pinfunction "1_1") (pintype "passive"))
      (node (ref "C147") (pin "1") (pinfunction "1_1") (pintype "passive"))
      (node (ref "C148") (pin "1") (pinfunction "1_1") (pintype "passive"))
      (node (ref "C149") (pin "1") (pinfunction "1_1") (pintype "passive"))
      (node (ref "C150") (pin "1") (pinfunction "1_1") (pintype "passive"))
      (node (ref "C151") (pin "1") (pinfunction "1_1") (pintype "passive"))
      (node (ref "C152") (pin "1") (pinfunction "1_1") (pintype "passive"))
      (node (ref "C153") (pin "1") (pinfunction "1_1") (pintype "passive"))
      (node (ref "C154") (pin "1") (pinfunction "1_1") (pintype "passive"))
      (node (ref "C155") (pin "1") (pinfunction "1_1") (pintype "passive"))
      (node (ref "C156") (pin "1") (pinfunction "1_1") (pintype "passive"))
      (node (ref "C157") (pin "1") (pinfunction "1_1") (pintype "passive"))
      (node (ref "C158") (pin "1") (pinfunction "1_1") (pintype "passive"))
      (node (ref "C159") (pin "1") (pinfunction "1_1") (pintype "passive"))
      (node (ref "C160") (pin "1") (pinfunction "1_1") (pintype "passive"))
      (node (ref "C161") (pin "1") (pinfunction "1_1") (pintype "passive"))
      (node (ref "C162") (pin "1") (pinfunction "1_1") (pintype "passive"))
      (node (ref "C163") (pin "1") (pinfunction "1_1") (pintype "passive"))
      (node (ref "C165") (pin "2") (pinfunction "2_2") (pintype "passive"))
      (node (ref "C166") (pin "2") (pinfunction "2_2") (pintype "passive"))
      (node (ref "C167") (pin "1") (pinfunction "1_1") (pintype "passive"))
      (node (ref "C168") (pin "1") (pinfunction "1_1") (pintype "passive"))
      (node (ref "C169") (pin "1") (pinfunction "1_1") (pintype "passive"))
      (node (ref "C170") (pin "1") (pinfunction "1_1") (pintype "passive"))
      (node (ref "C171") (pin "1") (pinfunction "1_1") (pintype "passive"))
      (node (ref "C172") (pin "1") (pinfunction "1_1") (pintype "passive"))
      (node (ref "C173") (pin "1") (pinfunction "1_1") (pintype "passive"))
      (node (ref "C174") (pin "1") (pinfunction "1_1") (pintype "passive"))
      (node (ref "C175") (pin "1") (pinfunction "1_1") (pintype "passive"))
      (node (ref "C176") (pin "1") (pinfunction "1_1") (pintype "passive"))
      (node (ref "C177") (pin "1") (pinfunction "1_1") (pintype "passive"))
      (node (ref "C178") (pin "1") (pinfunction "1_1") (pintype "passive"))
      (node (ref "C179") (pin "1") (pinfunction "1_1") (pintype "passive"))
      (node (ref "C180") (pin "1") (pinfunction "1_1") (pintype "passive"))
      (node (ref "C181") (pin "1") (pinfunction "1_1") (pintype "passive"))
      (node (ref "C182") (pin "1") (pinfunction "1_1") (pintype "passive"))
      (node (ref "C183") (pin "1") (pinfunction "1_1") (pintype "passive"))
      (node (ref "C184") (pin "1") (pinfunction "1_1") (pintype "passive"))
      (node (ref "C185") (pin "1") (pinfunction "1_1") (pintype "passive"))
      (node (ref "C186") (pin "1") (pinfunction "1_1") (pintype "passive"))
      (node (ref "C187") (pin "1") (pinfunction "1_1") (pintype "passive"))
      (node (ref "C188") (pin "1") (pinfunction "1_1") (pintype "passive"))
      (node (ref "C189") (pin "1") (pinfunction "1_1") (pintype "passive"))
      (node (ref "C190") (pin "1") (pinfunction "1_1") (pintype "passive"))
      (node (ref "C191") (pin "1") (pinfunction "1_1") (pintype "passive"))
      (node (ref "C192") (pin "1") (pinfunction "1_1") (pintype "passive"))
      (node (ref "C194") (pin "2") (pinfunction "2_2") (pintype "passive"))
      (node (ref "C195") (pin "2") (pinfunction "2_2") (pintype "passive"))
      (node (ref "C196") (pin "1") (pinfunction "1_1") (pintype "passive"))
      (node (ref "C197") (pin "1") (pinfunction "1_1") (pintype "passive"))
      (node (ref "C198") (pin "1") (pinfunction "1_1") (pintype "passive"))
      (node (ref "C199") (pin "1") (pinfunction "1_1") (pintype "passive"))
      (node (ref "C201") (pin "2") (pinfunction "2_2") (pintype "passive"))
      (node (ref "C202") (pin "2") (pinfunction "2_2") (pintype "passive"))
      (node (ref "C203") (pin "1") (pinfunction "1_1") (pintype "passive"))
      (node (ref "C204") (pin "1") (pinfunction "1_1") (pintype "passive"))
      (node (ref "C205") (pin "1") (pinfunction "1_1") (pintype "passive"))
      (node (ref "C206") (pin "2") (pinfunction "2_2") (pintype "passive"))
      (node (ref "C207") (pin "1") (pinfunction "1_1") (pintype "passive"))
      (node (ref "C208") (pin "2") (pinfunction "2_2") (pintype "passive"))
      (node (ref "C209") (pin "2") (pinfunction "2_2") (pintype "passive"))
      (node (ref "C210") (pin "1") (pinfunction "1_1") (pintype "passive"))
      (node (ref "C211") (pin "2") (pinfunction "2_2") (pintype "passive"))
      (node (ref "C212") (pin "2") (pinfunction "2_2") (pintype "passive"))
      (node (ref "C213") (pin "1") (pinfunction "1_1") (pintype "passive"))
      (node (ref "C216") (pin "1") (pinfunction "1_1") (pintype "passive"))
      (node (ref "C217") (pin "1") (pinfunction "1_1") (pintype "passive"))
      (node (ref "U1") (pin "A1") (pinfunction "GND_A1") (pintype "power_in"))
      (node (ref "U1") (pin "A22") (pinfunction "GND_A22") (pintype "power_in"))
      (node (ref "U1") (pin "AA13") (pinfunction "GND_AA13") (pintype "power_in"))
      (node (ref "U1") (pin "AA17") (pinfunction "GND_AA17") (pintype "power_in"))
      (node (ref "U1") (pin "AA5") (pinfunction "GND_AA5") (pintype "power_in"))
      (node (ref "U1") (pin "AA9") (pinfunction "GND_AA9") (pintype "power_in"))
      (node (ref "U1") (pin "AB1") (pinfunction "GND_AB1") (pintype "power_in"))
      (node (ref "U1") (pin "AB22") (pinfunction "GND_AB22") (pintype "power_in"))
      (node (ref "U1") (pin "B13") (pinfunction "GND_B13") (pintype "power_in"))
      (node (ref "U1") (pin "B17") (pinfunction "GND_B17") (pintype "power_in"))
      (node (ref "U1") (pin "B5") (pinfunction "GND_B5") (pintype "power_in"))
      (node (ref "U1") (pin "B9") (pinfunction "GND_B9") (pintype "power_in"))
      (node (ref "U1") (pin "D18") (pinfunction "GND_D18") (pintype "power_in"))
      (node (ref "U1") (pin "D4") (pinfunction "GND_D4") (pintype "power_in"))
      (node (ref "U1") (pin "E11") (pinfunction "GND_E11") (pintype "power_in"))
      (node (ref "U1") (pin "E15") (pinfunction "GND_E15") (pintype "power_in"))
      (node (ref "U1") (pin "E2") (pinfunction "GND_E2") (pintype "power_in"))
      (node (ref "U1") (pin "E21") (pinfunction "GND_E21") (pintype "power_in"))
      (node (ref "U1") (pin "E7") (pinfunction "GND_E7") (pintype "power_in"))
      (node (ref "U1") (pin "G18") (pinfunction "GND_G18") (pintype "power_in"))
      (node (ref "U1") (pin "G5") (pinfunction "GND_G5") (pintype "power_in"))
      (node (ref "U1") (pin "H7") (pinfunction "GND_H7") (pintype "power_in"))
      (node (ref "U1") (pin "J11") (pinfunction "GND_J11") (pintype "power_in"))
      (node (ref "U1") (pin "J13") (pinfunction "GND_J13") (pintype "power_in"))
      (node (ref "U1") (pin "J15") (pinfunction "GND_J15") (pintype "power_in"))
      (node (ref "U1") (pin "J2") (pinfunction "GND_J2") (pintype "power_in"))
      (node (ref "U1") (pin "J21") (pinfunction "GND_J21") (pintype "power_in"))
      (node (ref "U1") (pin "J9") (pinfunction "GND_J9") (pintype "power_in"))
      (node (ref "U1") (pin "K10") (pinfunction "GND_K10") (pintype "power_in"))
      (node (ref "U1") (pin "K12") (pinfunction "GND_K12") (pintype "power_in"))
      (node (ref "U1") (pin "K14") (pinfunction "GND_K14") (pintype "power_in"))
      (node (ref "U1") (pin "L11") (pinfunction "GND_L11") (pintype "power_in"))
      (node (ref "U1") (pin "L13") (pinfunction "GND_L13") (pintype "power_in"))
      (node (ref "U1") (pin "L18") (pinfunction "GND_L18") (pintype "power_in"))
      (node (ref "U1") (pin "L5") (pinfunction "GND_L5") (pintype "power_in"))
      (node (ref "U1") (pin "L9") (pinfunction "GND_L9") (pintype "power_in"))
      (node (ref "U1") (pin "M10") (pinfunction "GND_M10") (pintype "power_in"))
      (node (ref "U1") (pin "M12") (pinfunction "GND_M12") (pintype "power_in"))
      (node (ref "U1") (pin "M14") (pinfunction "GND_M14") (pintype "power_in"))
      (node (ref "U1") (pin "N11") (pinfunction "GND_N11") (pintype "power_in"))
      (node (ref "U1") (pin "N13") (pinfunction "GND_N13") (pintype "power_in"))
      (node (ref "U1") (pin "N17") (pinfunction "GND_N17") (pintype "power_in"))
      (node (ref "U1") (pin "N2") (pinfunction "GND_N2") (pintype "power_in"))
      (node (ref "U1") (pin "N21") (pinfunction "GND_N21") (pintype "power_in"))
      (node (ref "U1") (pin "N9") (pinfunction "GND_N9") (pintype "power_in"))
      (node (ref "U1") (pin "P10") (pinfunction "GND_P10") (pintype "power_in"))
      (node (ref "U1") (pin "P12") (pinfunction "GND_P12") (pintype "power_in"))
      (node (ref "U1") (pin "P14") (pinfunction "GND_P14") (pintype "power_in"))
      (node (ref "U1") (pin "R18") (pinfunction "GND_R18") (pintype "power_in"))
      (node (ref "U1") (pin "R5") (pinfunction "GND_R5") (pintype "power_in"))
      (node (ref "U1") (pin "U2") (pinfunction "GND_U2") (pintype "power_in"))
      (node (ref "U1") (pin "U21") (pinfunction "GND_U21") (pintype "power_in"))
      (node (ref "U1") (pin "U7") (pinfunction "GND_U7") (pintype "power_in"))
      (node (ref "U1") (pin "V10") (pinfunction "GND_V10") (pintype "power_in"))
      (node (ref "U1") (pin "V14") (pinfunction "GND_V14") (pintype "power_in"))
      (node (ref "U1") (pin "V4") (pinfunction "GND_V4") (pintype "power_in"))
      (node (ref "U1") (pin "W16") (pinfunction "GND_W16") (pintype "power_in"))
      (node (ref "U1") (pin "W19") (pinfunction "GND_W19") (pintype "power_in"))
      (node (ref "U1") (pin "W7") (pinfunction "GND_W7") (pintype "power_in"))
      (node (ref "U15") (pin "1") (pinfunction "AGND_1") (pintype "passive"))
      (node (ref "U15") (pin "11") (pinfunction "PGND_11") (pintype "passive"))
      (node (ref "U15") (pin "12") (pinfunction "PGND_12") (pintype "passive"))
      (node (ref "U15") (pin "13") (pinfunction "PGND_13") (pintype "passive"))
      (node (ref "U16") (pin "1") (pinfunction "AGND_1") (pintype "passive"))
      (node (ref "U16") (pin "11") (pinfunction "PGND_11") (pintype "passive"))
      (node (ref "U16") (pin "12") (pinfunction "PGND_12") (pintype "passive"))
      (node (ref "U16") (pin "13") (pinfunction "PGND_13") (pintype "passive"))
      (node (ref "U17") (pin "1") (pinfunction "AGND_1") (pintype "passive"))
      (node (ref "U17") (pin "11") (pinfunction "PGND_11") (pintype "passive"))
      (node (ref "U17") (pin "12") (pinfunction "PGND_12") (pintype "passive"))
      (node (ref "U17") (pin "13") (pinfunction "PGND_13") (pintype "passive"))
      (node (ref "U18") (pin "3") (pinfunction "GND_3") (pintype "power_in"))
      (node (ref "U18") (pin "6") (pinfunction "GND_6") (pintype "power_in"))
      (node (ref "U18") (pin "7") (pinfunction "GND_7") (pintype "power_in"))
      (node (ref "U19") (pin "1") (pinfunction "GND_1") (pintype "power_in"))
      (node (ref "X1") (pin "2") (pinfunction "2_2") (pintype "passive"))
    )
    (net (code "4") (name "Net-(C164-Pad1)") (class "Default")
      (node (ref "C164") (pin "1") (pinfunction "1_1") (pintype "passive"))
      (node (ref "L6") (pin "2") (pinfunction "2_2") (pintype "passive"))
      (node (ref "U15") (pin "10") (pinfunction "PH_10") (pintype "passive"))
      (node (ref "U15") (pin "6") (pinfunction "PH_6") (pintype "passive"))
      (node (ref "U15") (pin "7") (pinfunction "PH_7") (pintype "passive"))
      (node (ref "U15") (pin "8") (pinfunction "PH_8") (pintype "passive"))
      (node (ref "U15") (pin "9") (pinfunction "PH_9") (pintype "passive"))
    )
    (net (code "5") (name "Net-(C193-Pad1)") (class "Default")
      (node (ref "C193") (pin "1") (pinfunction "1_1") (pintype "passive"))
      (node (ref "L7") (pin "2") (pinfunction "2_2") (pintype "passive"))
      (node (ref "U16") (pin "10") (pinfunction "PH_10") (pintype "passive"))
      (node (ref "U16") (pin "6") (pinfunction "PH_6") (pintype "passive"))
      (node (ref "U16") (pin "7") (pinfunction "PH_7") (pintype "passive"))
      (node (ref "U16") (pin "8") (pinfunction "PH_8") (pintype "passive"))
      (node (ref "U16") (pin "9") (pinfunction "PH_9") (pintype "passive"))
    )
    (net (code "6") (name "Net-(C200-Pad1)") (class "Default")
      (node (ref "C200") (pin "1") (pinfunction "1_1") (pintype "passive"))
      (node (ref "L8") (pin "2") (pinfunction "2_2") (pintype "passive"))
      (node (ref "U17") (pin "10") (pinfunction "PH_10") (pintype "passive"))
      (node (ref "U17") (pin "6") (pinfunction "PH_6") (pintype "passive"))
      (node (ref "U17") (pin "7") (pinfunction "PH_7") (pintype "passive"))
      (node (ref "U17") (pin "8") (pinfunction "PH_8") (pintype "passive"))
      (node (ref "U17") (pin "9") (pinfunction "PH_9") (pintype "passive"))
    )
    (net (code "7") (name "Net-(U15-BOOT)") (class "Default")
      (node (ref "C164") (pin "2") (pinfunction "2_2") (pintype "passive"))
      (node (ref "U15") (pin "5") (pinfunction "BOOT_5") (pintype "passive"))
    )
    (net (code "8") (name "Net-(U15-VBIAS)") (class "Default")
      (node (ref "C163") (pin "2") (pinfunction "2_2") (pintype "passive"))
      (node (ref "U15") (pin "17") (pinfunction "VBIAS_17") (pintype "passive"))
    )
    (net (code "9") (name "Net-(U15-Vsense)") (class "Default")
      (node (ref "C166") (pin "1") (pinfunction "1_1") (pintype "passive"))
      (node (ref "C167") (pin "2") (pinfunction "2_2") (pintype "passive"))
      (node (ref "C168") (pin "2") (pinfunction "2_2") (pintype "passive"))
      (node (ref "C169") (pin "2") (pinfunction "2_2") (pintype "passive"))
      (node (ref "C170") (pin "2") (pinfunction "2_2") (pintype "passive"))
      (node (ref "L6") (pin "1") (pinfunction "1_1") (pintype "passive"))
      (node (ref "R75") (pin "1") (pinfunction "1_1") (pintype "passive"))
      (node (ref "U15") (pin "2") (pinfunction "Vsense_2") (pintype "passive"))
    )
    (net (code "10") (name "Net-(U16-BOOT)") (class "Default")
      (node (ref "C193") (pin "2") (pinfunction "2_2") (pintype "passive"))
      (node (ref "U16") (pin "5") (pinfunction "BOOT_5") (pintype "passive"))
    )
    (net (code "11") (name "Net-(U16-VBIAS)") (class "Default")
      (node (ref "C192") (pin "2") (pinfunction "2_2") (pintype "passive"))
      (node (ref "U16") (pin "17") (pinfunction "VBIAS_17") (pintype "passive"))
    )
    (net (code "12") (name "Net-(U16-Vsense)") (class "Default")
      (node (ref "C195") (pin "1") (pinfunction "1_1") (pintype "passive"))
      (node (ref "C196") (pin "2") (pinfunction "2_2") (pintype "passive"))
      (node (ref "C197") (pin "2") (pinfunction "2_2") (pintype "passive"))
      (node (ref "C198") (pin "2") (pinfunction "2_2") (pintype "passive"))
      (node (ref "L7") (pin "1") (pinfunction "1_1") (pintype "passive"))
      (node (ref "R76") (pin "1") (pinfunction "1_1") (pintype "passive"))
      (node (ref "U16") (pin "2") (pinfunction "Vsense_2") (pintype "passive"))
    )
    (net (code "13") (name "Net-(U17-BOOT)") (class "Default")
      (node (ref "C200") (pin "2") (pinfunction "2_2") (pintype "passive"))
      (node (ref "U17") (pin "5") (pinfunction "BOOT_5") (pintype "passive"))
    )
    (net (code "14") (name "Net-(U17-VBIAS)") (class "Default")
      (node (ref "C199") (pin "2") (pinfunction "2_2") (pintype "passive"))
      (node (ref "U17") (pin "17") (pinfunction "VBIAS_17") (pintype "passive"))
    )
    (net (code "15") (name "Net-(U17-Vsense)") (class "Default")
      (node (ref "C202") (pin "1") (pinfunction "1_1") (pintype "passive"))
      (node (ref "C203") (pin "2") (pinfunction "2_2") (pintype "passive"))
      (node (ref "C204") (pin "2") (pinfunction "2_2") (pintype "passive"))
      (node (ref "C205") (pin "2") (pinfunction "2_2") (pintype "passive"))
      (node (ref "L8") (pin "1") (pinfunction "1_1") (pintype "passive"))
      (node (ref "R77") (pin "1") (pinfunction "1_1") (pintype "passive"))
      (node (ref "U17") (pin "2") (pinfunction "Vsense_2") (pintype "passive"))
    )
    (net (code "16") (name "Net-(U18-ADJ{slash}SENSE)") (class "Default")
      (node (ref "C209") (pin "1") (pinfunction "1_1") (pintype "passive"))
      (node (ref "C210") (pin "2") (pinfunction "2_2") (pintype "passive"))
      (node (ref "R78") (pin "2") (pinfunction "2_2") (pintype "passive"))
      (node (ref "U18") (pin "1") (pinfunction "OUT_1") (pintype "power_in"))
      (node (ref "U18") (pin "2") (pinfunction "ADJ/SENSE_2") (pintype "input"))
    )
    (net (code "17") (name "VCC1V2") (class "Default")
      (node (ref "C171") (pin "2") (pinfunction "2_2") (pintype "passive"))
      (node (ref "C172") (pin "2") (pinfunction "2_2") (pintype "passive"))
      (node (ref "C173") (pin "2") (pinfunction "2_2") (pintype "passive"))
      (node (ref "C174") (pin "2") (pinfunction "2_2") (pintype "passive"))
      (node (ref "C175") (pin "2") (pinfunction "2_2") (pintype "passive"))
      (node (ref "C176") (pin "2") (pinfunction "2_2") (pintype "passive"))
      (node (ref "C177") (pin "2") (pinfunction "2_2") (pintype "passive"))
      (node (ref "C178") (pin "2") (pinfunction "2_2") (pintype "passive"))
      (node (ref "C179") (pin "2") (pinfunction "2_2") (pintype "passive"))
      (node (ref "C180") (pin "2") (pinfunction "2_2") (pintype "passive"))
      (node (ref "C181") (pin "2") (pinfunction "2_2") (pintype "passive"))
      (node (ref "C182") (pin "2") (pinfunction "2_2") (pintype "passive"))
      (node (ref "C183") (pin "2") (pinfunction "2_2") (pintype "passive"))
      (node (ref "C184") (pin "2") (pinfunction "2_2") (pintype "passive"))
      (node (ref "C185") (pin "2") (pinfunction "2_2") (pintype "passive"))
      (node (ref "C186") (pin "2") (pinfunction "2_2") (pintype "passive"))
      (node (ref "C187") (pin "2") (pinfunction "2_2") (pintype "passive"))
      (node (ref "C188") (pin "2") (pinfunction "2_2") (pintype "passive"))
      (node (ref "C189") (pin "2") (pinfunction "2_2") (pintype "passive"))
      (node (ref "C190") (pin "2") (pinfunction "2_2") (pintype "passive"))
      (node (ref "C191") (pin "2") (pinfunction "2_2") (pintype "passive"))
      (node (ref "R77") (pin "2") (pinfunction "2_2") (pintype "passive"))
      (node (ref "U1") (pin "J10") (pinfunction "VCCINT_J10") (pintype "power_in"))
      (node (ref "U1") (pin "J12") (pinfunction "VCCINT_J12") (pintype "power_in"))
      (node (ref "U1") (pin "J14") (pinfunction "VCCINT_J14") (pintype "power_in"))
      (node (ref "U1") (pin "J8") (pinfunction "VCCINT_J8") (pintype "power_in"))
      (node (ref "U1") (pin "K11") (pinfunction "VCCINT_K11") (pintype "power_in"))
      (node (ref "U1") (pin "K13") (pinfunction "VCCINT_K13") (pintype "power_in"))
      (node (ref "U1") (pin "K9") (pinfunction "VCCINT_K9") (pintype "power_in"))
      (node (ref "U1") (pin "L10") (pinfunction "VCCINT_L10") (pintype "power_in"))
      (node (ref "U1") (pin "L12") (pinfunction "VCCINT_L12") (pintype "power_in"))
      (node (ref "U1") (pin "L14") (pinfunction "VCCINT_L14") (pintype "power_in"))
      (node (ref "U1") (pin "M11") (pinfunction "VCCINT_M11") (pintype "power_in"))
      (node (ref "U1") (pin "M13") (pinfunction "VCCINT_M13") (pintype "power_in"))
      (node (ref "U1") (pin "M9") (pinfunction "VCCINT_M9") (pintype "power_in"))
      (node (ref "U1") (pin "N10") (pinfunction "VCCINT_N10") (pintype "power_in"))
      (node (ref "U1") (pin "N12") (pinfunction "VCCINT_N12") (pintype "power_in"))
      (node (ref "U1") (pin "N14") (pinfunction "VCCINT_N14") (pintype "power_in"))
      (node (ref "U1") (pin "P11") (pinfunction "VCCINT_P11") (pintype "power_in"))
      (node (ref "U1") (pin "P13") (pinfunction "VCCINT_P13") (pintype "power_in"))
      (node (ref "U1") (pin "P9") (pinfunction "VCCINT_P9") (pintype "power_in"))
      (node (ref "U1") (pin "R14") (pinfunction "VCCINT_R14") (pintype "power_in"))
    )
    (net (code "18") (name "VCC1V8") (class "Default")
      (node (ref "C151") (pin "2") (pinfunction "2_2") (pintype "passive"))
      (node (ref "C152") (pin "2") (pinfunction "2_2") (pintype "passive"))
      (node (ref "C153") (pin "2") (pinfunction "2_2") (pintype "passive"))
      (node (ref "C154") (pin "2") (pinfunction "2_2") (pintype "passive"))
      (node (ref "C155") (pin "2") (pinfunction "2_2") (pintype "passive"))
      (node (ref "C156") (pin "2") (pinfunction "2_2") (pintype "passive"))
      (node (ref "C157") (pin "2") (pinfunction "2_2") (pintype "passive"))
      (node (ref "C158") (pin "2") (pinfunction "2_2") (pintype "passive"))
      (node (ref "C159") (pin "2") (pinfunction "2_2") (pintype "passive"))
      (node (ref "C160") (pin "2") (pinfunction "2_2") (pintype "passive"))
      (node (ref "C161") (pin "2") (pinfunction "2_2") (pintype "passive"))
      (node (ref "C162") (pin "2") (pinfunction "2_2") (pintype "passive"))
      (node (ref "C211") (pin "1") (pinfunction "1_1") (pintype "passive"))
      (node (ref "R75") (pin "2") (pinfunction "2_2") (pintype "passive"))
      (node (ref "U1") (pin "C2") (pinfunction "VCCO_3_C2") (pintype "power_in"))
      (node (ref "U1") (pin "F4") (pinfunction "VCCO_3_F4") (pintype "power_in"))
      (node (ref "U1") (pin "F6") (pinfunction "VCCO_3_F6") (pintype "power_in"))
      (node (ref "U1") (pin "G2") (pinfunction "VCCO_3_G2") (pintype "power_in"))
      (node (ref "U1") (pin "J5") (pinfunction "VCCO_3_J5") (pintype "power_in"))
      (node (ref "U1") (pin "L2") (pinfunction "VCCO_3_L2") (pintype "power_in"))
      (node (ref "U1") (pin "L7") (pinfunction "VCCO_3_L7") (pintype "power_in"))
      (node (ref "U1") (pin "N5") (pinfunction "VCCO_3_N5") (pintype "power_in"))
      (node (ref "U1") (pin "R2") (pinfunction "VCCO_3_R2") (pintype "power_in"))
      (node (ref "U1") (pin "U5") (pinfunction "VCCO_3_U5") (pintype "power_in"))
      (node (ref "U1") (pin "W2") (pinfunction "VCCO_3_W2") (pintype "power_in"))
      (node (ref "U19") (pin "5") (pinfunction "VDDQ_5") (pintype "power_in"))
      (node (ref "U19") (pin "7") (pinfunction "PVIN_7") (pintype "power_in"))
    )
    (net (code "19") (name "VCC2V5") (class "Default")
      (node (ref "R78") (pin "1") (pinfunction "1_1") (pintype "passive"))
    )
    (net (code "20") (name "VCC3V3") (class "Default")
      (node (ref "C105") (pin "2") (pinfunction "2_2") (pintype "passive"))
      (node (ref "C106") (pin "2") (pinfunction "2_2") (pintype "passive"))
      (node (ref "C107") (pin "2") (pinfunction "2_2") (pintype "passive"))
      (node (ref "C108") (pin "2") (pinfunction "2_2") (pintype "passive"))
      (node (ref "C109") (pin "2") (pinfunction "2_2") (pintype "passive"))
      (node (ref "C110") (pin "2") (pinfunction "2_2") (pintype "passive"))
      (node (ref "C111") (pin "2") (pinfunction "2_2") (pintype "passive"))
      (node (ref "C112") (pin "2") (pinfunction "2_2") (pintype "passive"))
      (node (ref "C113") (pin "2") (pinfunction "2_2") (pintype "passive"))
      (node (ref "C114") (pin "2") (pinfunction "2_2") (pintype "passive"))
      (node (ref "C115") (pin "2") (pinfunction "2_2") (pintype "passive"))
      (node (ref "C116") (pin "2") (pinfunction "2_2") (pintype "passive"))
      (node (ref "C117") (pin "2") (pinfunction "2_2") (pintype "passive"))
      (node (ref "C118") (pin "2") (pinfunction "2_2") (pintype "passive"))
      (node (ref "C119") (pin "2") (pinfunction "2_2") (pintype "passive"))
      (node (ref "C120") (pin "2") (pinfunction "2_2") (pintype "passive"))
      (node (ref "C121") (pin "2") (pinfunction "2_2") (pintype "passive"))
      (node (ref "C122") (pin "2") (pinfunction "2_2") (pintype "passive"))
      (node (ref "C123") (pin "2") (pinfunction "2_2") (pintype "passive"))
      (node (ref "C124") (pin "2") (pinfunction "2_2") (pintype "passive"))
      (node (ref "C125") (pin "2") (pinfunction "2_2") (pintype "passive"))
      (node (ref "C126") (pin "2") (pinfunction "2_2") (pintype "passive"))
      (node (ref "C127") (pin "2") (pinfunction "2_2") (pintype "passive"))
      (node (ref "C128") (pin "2") (pinfunction "2_2") (pintype "passive"))
      (node (ref "C129") (pin "2") (pinfunction "2_2") (pintype "passive"))
      (node (ref "C130") (pin "2") (pinfunction "2_2") (pintype "passive"))
      (node (ref "C131") (pin "2") (pinfunction "2_2") (pintype "passive"))
      (node (ref "C132") (pin "2") (pinfunction "2_2") (pintype "passive"))
      (node (ref "C133") (pin "2") (pinfunction "2_2") (pintype "passive"))
      (node (ref "C134") (pin "2") (pinfunction "2_2") (pintype "passive"))
      (node (ref "C135") (pin "2") (pinfunction "2_2") (pintype "passive"))
      (node (ref "C136") (pin "2") (pinfunction "2_2") (pintype "passive"))
      (node (ref "C137") (pin "2") (pinfunction "2_2") (pintype "passive"))
      (node (ref "C138") (pin "2") (pinfunction "2_2") (pintype "passive"))
      (node (ref "C139") (pin "2") (pinfunction "2_2") (pintype "passive"))
      (node (ref "C140") (pin "2") (pinfunction "2_2") (pintype "passive"))
      (node (ref "C141") (pin "2") (pinfunction "2_2") (pintype "passive"))
      (node (ref "C142") (pin "2") (pinfunction "2_2") (pintype "passive"))
      (node (ref "C143") (pin "2") (pinfunction "2_2") (pintype "passive"))
      (node (ref "C144") (pin "2") (pinfunction "2_2") (pintype "passive"))
      (node (ref "C145") (pin "2") (pinfunction "2_2") (pintype "passive"))
      (node (ref "C146") (pin "2") (pinfunction "2_2") (pintype "passive"))
      (node (ref "C147") (pin "2") (pinfunction "2_2") (pintype "passive"))
      (node (ref "C148") (pin "2") (pinfunction "2_2") (pintype "passive"))
      (node (ref "C149") (pin "2") (pinfunction "2_2") (pintype "passive"))
      (node (ref "C150") (pin "2") (pinfunction "2_2") (pintype "passive"))
      (node (ref "C216") (pin "2") (pinfunction "2_2") (pintype "passive"))
      (node (ref "C217") (pin "2") (pinfunction "2_2") (pintype "passive"))
      (node (ref "R76") (pin "2") (pinfunction "2_2") (pintype "passive"))
      (node (ref "U1") (pin "AA11") (pinfunction "VCCO_2_AA11") (pintype "power_in"))
      (node (ref "U1") (pin "AA15") (pinfunction "VCCO_2_AA15") (pintype "power_in"))
      (node (ref "U1") (pin "AA19") (pinfunction "VCCO_2_AA19") (pintype "power_in"))
      (node (ref "U1") (pin "AA3") (pinfunction "VCCO_2_AA3") (pintype "power_in"))
      (node (ref "U1") (pin "AA7") (pinfunction "VCCO_2_AA7") (pintype "power_in"))
      (node (ref "U1") (pin "B11") (pinfunction "VCCO_0_B11") (pintype "power_in"))
      (node (ref "U1") (pin "B15") (pinfunction "VCCO_0_B15") (pintype "power_in"))
      (node (ref "U1") (pin "B19") (pinfunction "VCCO_0_B19") (pintype "power_in"))
      (node (ref "U1") (pin "B4") (pinfunction "VCCO_0_B4") (pintype "power_in"))
      (node (ref "U1") (pin "B7") (pinfunction "VCCO_0_B7") (pintype "power_in"))
      (node (ref "U1") (pin "C21") (pinfunction "VCCO_1_C21") (pintype "power_in"))
      (node (ref "U1") (pin "D16") (pinfunction "VCCAUX_D16") (pintype "power_in"))
      (node (ref "U1") (pin "E13") (pinfunction "VCCO_0_E13") (pintype "power_in"))
      (node (ref "U1") (pin "E17") (pinfunction "VCCO_0_E17") (pintype "power_in"))
      (node (ref "U1") (pin "E19") (pinfunction "VCCO_1_E19") (pintype "power_in"))
      (node (ref "U1") (pin "E9") (pinfunction "VCCO_0_E9") (pintype "power_in"))
      (node (ref "U1") (pin "F11") (pinfunction "VCCAUX_F11") (pintype "power_in"))
      (node (ref "U1") (pin "G10") (pinfunction "VCCO_0_G10") (pintype "power_in"))
      (node (ref "U1") (pin "G12") (pinfunction "VCCAUX_G12") (pintype "power_in"))
      (node (ref "U1") (pin "G14") (pinfunction "VCCO_0_G14") (pintype "power_in"))
      (node (ref "U1") (pin "G21") (pinfunction "VCCO_1_G21") (pintype "power_in"))
      (node (ref "U1") (pin "H15") (pinfunction "VCCAUX_H15") (pintype "power_in"))
      (node (ref "U1") (pin "H9") (pinfunction "VCCAUX_H9") (pintype "power_in"))
      (node (ref "U1") (pin "J18") (pinfunction "VCCO_1_J18") (pintype "power_in"))
      (node (ref "U1") (pin "K15") (pinfunction "VCCAUX_K15") (pintype "power_in"))
      (node (ref "U1") (pin "L16") (pinfunction "VCCO_1_L16") (pintype "power_in"))
      (node (ref "U1") (pin "L21") (pinfunction "VCCO_1_L21") (pintype "power_in"))
      (node (ref "U1") (pin "L8") (pinfunction "VCCAUX_L8") (pintype "power_in"))
      (node (ref "U1") (pin "M15") (pinfunction "VCCAUX_M15") (pintype "power_in"))
      (node (ref "U1") (pin "N18") (pinfunction "VCCO_1_N18") (pintype "power_in"))
      (node (ref "U1") (pin "N8") (pinfunction "VCCAUX_N8") (pintype "power_in"))
      (node (ref "U1") (pin "R10") (pinfunction "VCCAUX_R10") (pintype "power_in"))
      (node (ref "U1") (pin "R12") (pinfunction "VCCAUX_R12") (pintype "power_in"))
      (node (ref "U1") (pin "R21") (pinfunction "VCCO_1_R21") (pintype "power_in"))
      (node (ref "U1") (pin "R6") (pinfunction "VCCAUX_R6") (pintype "power_in"))
      (node (ref "U1") (pin "T13") (pinfunction "VCCO_2_T13") (pintype "power_in"))
      (node (ref "U1") (pin "T9") (pinfunction "VCCO_2_T9") (pintype "power_in"))
      (node (ref "U1") (pin "U11") (pinfunction "VCCAUX_U11") (pintype "power_in"))
      (node (ref "U1") (pin "U18") (pinfunction "VCCO_1_U18") (pintype "power_in"))
      (node (ref "U1") (pin "V12") (pinfunction "VCCO_2_V12") (pintype "power_in"))
      (node (ref "U1") (pin "V16") (pinfunction "VCCO_2_V16") (pintype "power_in"))
      (node (ref "U1") (pin "V6") (pinfunction "VCCAUX_V6") (pintype "power_in"))
      (node (ref "U1") (pin "V8") (pinfunction "VCCO_2_V8") (pintype "power_in"))
      (node (ref "U1") (pin "W21") (pinfunction "VCCO_1_W21") (pintype "power_in"))
      (node (ref "U1") (pin "W5") (pinfunction "VCCO_2_W5") (pintype "power_in"))
      (node (ref "U19") (pin "2") (pinfunction "~{SD}_2") (pintype "input"))
      (node (ref "U19") (pin "6") (pinfunction "AVIN_6") (pintype "power_in"))
    )
    (net (code "21") (name "VCC5V") (class "Default")
      (node (ref "C165") (pin "1") (pinfunction "1_1") (pintype "passive"))
      (node (ref "C194") (pin "1") (pinfunction "1_1") (pintype "passive"))
      (node (ref "C201") (pin "1") (pinfunction "1_1") (pintype "passive"))
      (node (ref "C208") (pin "1") (pinfunction "1_1") (pintype "passive"))
      (node (ref "U15") (pin "14") (pinfunction "VIN_14") (pintype "passive"))
      (node (ref "U15") (pin "15") (pinfunction "VIN_15") (pintype "passive"))
      (node (ref "U15") (pin "16") (pinfunction "VIN_16") (pintype "passive"))
      (node (ref "U15") (pin "19") (pinfunction "FSEL_19") (pintype "passive"))
      (node (ref "U16") (pin "14") (pinfunction "VIN_14") (pintype "passive"))
      (node (ref "U16") (pin "15") (pinfunction "VIN_15") (pintype "passive"))
      (node (ref "U16") (pin "16") (pinfunction "VIN_16") (pintype "passive"))
      (node (ref "U16") (pin "19") (pinfunction "FSEL_19") (pintype "passive"))
      (node (ref "U17") (pin "14") (pinfunction "VIN_14") (pintype "passive"))
      (node (ref "U17") (pin "15") (pinfunction "VIN_15") (pintype "passive"))
      (node (ref "U17") (pin "16") (pinfunction "VIN_16") (pintype "passive"))
      (node (ref "U17") (pin "19") (pinfunction "FSEL_19") (pintype "passive"))
      (node (ref "U18") (pin "5") (pinfunction "~{SHDN}_5") (pintype "input"))
      (node (ref "U18") (pin "8") (pinfunction "IN_8") (pintype "power_in"))
      (node (ref "X1") (pin "1") (pinfunction "1_1") (pintype "passive"))
    )
    (net (code "22") (name "unconnected-(U1H-NC-PadD12)") (class "Default")
      (node (ref "U1") (pin "D12") (pinfunction "NC_D12") (pintype "passive"))
    )
    (net (code "23") (name "unconnected-(U1H-NC-PadD13)") (class "Default")
      (node (ref "U1") (pin "D13") (pinfunction "NC_D13") (pintype "passive"))
    )
    (net (code "24") (name "unconnected-(U1H-NC-PadE8)") (class "Default")
      (node (ref "U1") (pin "E8") (pinfunction "NC_E8") (pintype "passive"))
    )
    (net (code "25") (name "unconnected-(U1H-NC-PadE10)") (class "Default")
      (node (ref "U1") (pin "E10") (pinfunction "NC_E10") (pintype "passive"))
    )
    (net (code "26") (name "unconnected-(U1H-NC-PadE12)") (class "Default")
      (node (ref "U1") (pin "E12") (pinfunction "NC_E12") (pintype "passive"))
    )
    (net (code "27") (name "unconnected-(U1H-NC-PadE14)") (class "Default")
      (node (ref "U1") (pin "E14") (pinfunction "NC_E14") (pintype "passive"))
    )
    (net (code "28") (name "unconnected-(U1H-NC-PadF8)") (class "Default")
      (node (ref "U1") (pin "F8") (pinfunction "NC_F8") (pintype "passive"))
    )
    (net (code "29") (name "unconnected-(U1H-NC-PadF9)") (class "Default")
      (node (ref "U1") (pin "F9") (pinfunction "NC_F9") (pintype "passive"))
    )
    (net (code "30") (name "unconnected-(U1H-NC-PadF10)") (class "Default")
      (node (ref "U1") (pin "F10") (pinfunction "NC_F10") (pintype "passive"))
    )
    (net (code "31") (name "unconnected-(U1H-NC-PadF12)") (class "Default")
      (node (ref "U1") (pin "F12") (pinfunction "NC_F12") (pintype "passive"))
    )
    (net (code "32") (name "unconnected-(U1H-NC-PadF13)") (class "Default")
      (node (ref "U1") (pin "F13") (pinfunction "NC_F13") (pintype "passive"))
    )
    (net (code "33") (name "unconnected-(U1H-NC-PadF14)") (class "Default")
      (node (ref "U1") (pin "F14") (pinfunction "NC_F14") (pintype "passive"))
    )
    (net (code "34") (name "unconnected-(U1H-NC-PadF15)") (class "Default")
      (node (ref "U1") (pin "F15") (pinfunction "NC_F15") (pintype "passive"))
    )
    (net (code "35") (name "unconnected-(U1H-NC-PadG8)") (class "Default")
      (node (ref "U1") (pin "G8") (pinfunction "NC_G8") (pintype "passive"))
    )
    (net (code "36") (name "unconnected-(U1H-NC-PadG9)") (class "Default")
      (node (ref "U1") (pin "G9") (pinfunction "NC_G9") (pintype "passive"))
    )
    (net (code "37") (name "unconnected-(U1H-NC-PadG11)") (class "Default")
      (node (ref "U1") (pin "G11") (pinfunction "NC_G11") (pintype "passive"))
    )
    (net (code "38") (name "unconnected-(U1H-NC-PadG13)") (class "Default")
      (node (ref "U1") (pin "G13") (pinfunction "NC_G13") (pintype "passive"))
    )
    (net (code "39") (name "unconnected-(U1H-NC-PadH10)") (class "Default")
      (node (ref "U1") (pin "H10") (pinfunction "NC_H10") (pintype "passive"))
    )
    (net (code "40") (name "unconnected-(U1H-NC-PadH11)") (class "Default")
      (node (ref "U1") (pin "H11") (pinfunction "NC_H11") (pintype "passive"))
    )
    (net (code "41") (name "unconnected-(U1H-NC-PadH12)") (class "Default")
      (node (ref "U1") (pin "H12") (pinfunction "NC_H12") (pintype "passive"))
    )
    (net (code "42") (name "unconnected-(U1H-NC-PadH13)") (class "Default")
      (node (ref "U1") (pin "H13") (pinfunction "NC_H13") (pintype "passive"))
    )
    (net (code "43") (name "unconnected-(U1H-NC-PadH14)") (class "Default")
      (node (ref "U1") (pin "H14") (pinfunction "NC_H14") (pintype "passive"))
    )
    (net (code "44") (name "unconnected-(U1H-NC-PadP15)") (class "Default")
      (node (ref "U1") (pin "P15") (pinfunction "NC_P15") (pintype "passive"))
    )
    (net (code "45") (name "unconnected-(U1H-NC-PadP16)") (class "Default")
      (node (ref "U1") (pin "P16") (pinfunction "NC_P16") (pintype "passive"))
    )
    (net (code "46") (name "unconnected-(U1H-NC-PadR17)") (class "Default")
      (node (ref "U1") (pin "R17") (pinfunction "NC_R17") (pintype "passive"))
    )
    (net (code "47") (name "unconnected-(U15-NC-Pad3)") (class "Default")
      (node (ref "U15") (pin "3") (pinfunction "NC_3") (pintype "passive"))
    )
    (net (code "48") (name "unconnected-(U15-PWRGD-Pad4)") (class "Default")
      (node (ref "U15") (pin "4") (pinfunction "PWRGD_4") (pintype "passive"))
    )
    (net (code "49") (name "unconnected-(U15-RT-Pad20)") (class "Default")
      (node (ref "U15") (pin "20") (pinfunction "RT_20") (pintype "passive"))
    )
    (net (code "50") (name "unconnected-(U15-SS{slash}ENA-Pad18)") (class "Default")
      (node (ref "U15") (pin "18") (pinfunction "SS/ENA_18") (pintype "passive"))
    )
    (net (code "51") (name "unconnected-(U16-NC-Pad3)") (class "Default")
      (node (ref "U16") (pin "3") (pinfunction "NC_3") (pintype "passive"))
    )
    (net (code "52") (name "unconnected-(U16-PWRGD-Pad4)") (class "Default")
      (node (ref "U16") (pin "4") (pinfunction "PWRGD_4") (pintype "passive"))
    )
    (net (code "53") (name "unconnected-(U16-RT-Pad20)") (class "Default")
      (node (ref "U16") (pin "20") (pinfunction "RT_20") (pintype "passive"))
    )
    (net (code "54") (name "unconnected-(U16-SS{slash}ENA-Pad18)") (class "Default")
      (node (ref "U16") (pin "18") (pinfunction "SS/ENA_18") (pintype "passive"))
    )
    (net (code "55") (name "unconnected-(U17-NC-Pad3)") (class "Default")
      (node (ref "U17") (pin "3") (pinfunction "NC_3") (pintype "passive"))
    )
    (net (code "56") (name "unconnected-(U17-PWRGD-Pad4)") (class "Default")
      (node (ref "U17") (pin "4") (pinfunction "PWRGD_4") (pintype "passive"))
    )
    (net (code "57") (name "unconnected-(U17-RT-Pad20)") (class "Default")
      (node (ref "U17") (pin "20") (pinfunction "RT_20") (pintype "passive"))
    )
    (net (code "58") (name "unconnected-(U17-SS{slash}ENA-Pad18)") (class "Default")
      (node (ref "U17") (pin "18") (pinfunction "SS/ENA_18") (pintype "passive"))
    )
    (net (code "59") (name "unconnected-(U18-NC-Pad4)") (class "Default")
      (node (ref "U18") (pin "4") (pinfunction "NC_4") (pintype "passive"))
    )
  )
)
